# PCB-REMCON-ER.net
KiCad netlist of a schematic drawn in EAGLE
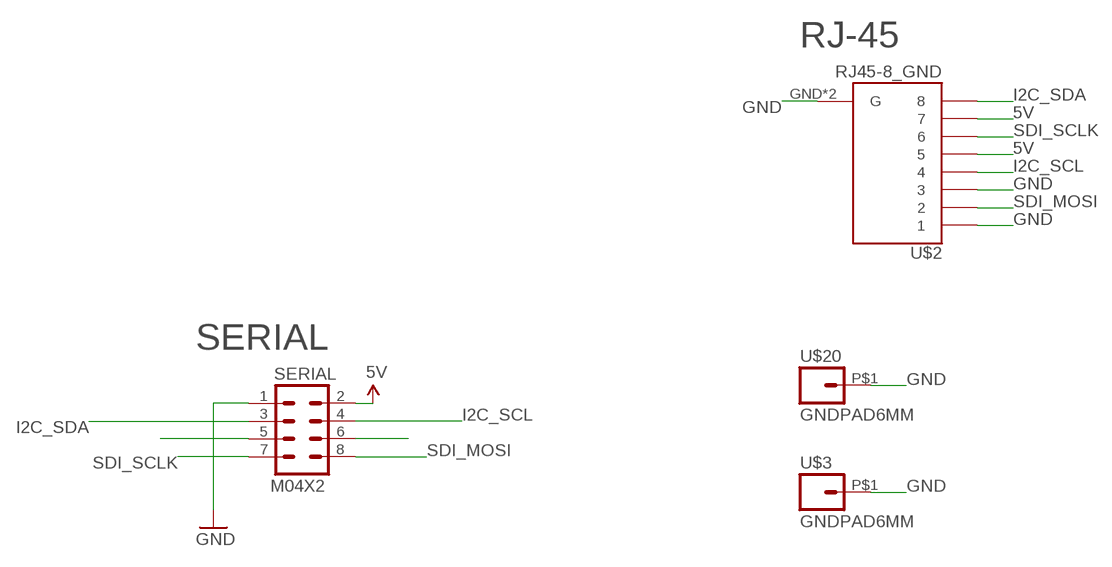
[diagram p0: schematic, sheet 1]

(export (version "E")
  (design (tool "Eeschema 10.0.6"))
  (components
    (comp (ref "SERIAL")
      (value "M04X2")
      (footprint "eagle-import:2X4")
      (libsource (lib "eagle-import") (part "M04X2"))
    )
    (comp (ref "U$2")
      (value "RJ45-8_GND")
      (footprint "eagle-import:RJ45-8_GND")
      (libsource (lib "eagle-import") (part "RJ45-8_GND"))
    )
    (comp (ref "U$3")
      (value "GNDPAD6MM")
      (footprint "eagle-import:3.2MMPAD6MM")
      (libsource (lib "eagle-import") (part "GNDPAD6MM"))
    )
    (comp (ref "U$20")
      (value "GNDPAD6MM")
      (footprint "eagle-import:3.2MMPAD6MM")
      (libsource (lib "eagle-import") (part "GNDPAD6MM"))
    )
  )
  (nets
    (net (code "1") (name "/I2C_SCL") (class "Default")
      (node (ref "SERIAL") (pin "4") (pinfunction "4_4") (pintype "passive"))
      (node (ref "U$2") (pin "4") (pinfunction "4_4") (pintype "bidirectional"))
    )
    (net (code "2") (name "/I2C_SDA") (class "Default")
      (node (ref "SERIAL") (pin "3") (pinfunction "3_3") (pintype "passive"))
      (node (ref "U$2") (pin "8") (pinfunction "8_8") (pintype "bidirectional"))
    )
    (net (code "3") (name "/SDI_MOSI") (class "Default")
      (node (ref "SERIAL") (pin "8") (pinfunction "8_8") (pintype "passive"))
      (node (ref "U$2") (pin "2") (pinfunction "2_2") (pintype "bidirectional"))
    )
    (net (code "4") (name "/SDI_SCLK") (class "Default")
      (node (ref "SERIAL") (pin "7") (pinfunction "7_7") (pintype "passive"))
      (node (ref "U$2") (pin "6") (pinfunction "6_6") (pintype "bidirectional"))
    )
    (net (code "5") (name "5V") (class "Default")
      (node (ref "SERIAL") (pin "2") (pinfunction "2_2") (pintype "passive"))
      (node (ref "U$2") (pin "5") (pinfunction "5_5") (pintype "bidirectional"))
      (node (ref "U$2") (pin "7") (pinfunction "7_7") (pintype "bidirectional"))
    )
    (net (code "6") (name "GND") (class "Default")
      (node (ref "SERIAL") (pin "1") (pinfunction "1_1") (pintype "passive"))
      (node (ref "U$2") (pin "1") (pinfunction "1_1") (pintype "bidirectional"))
      (node (ref "U$2") (pin "3") (pinfunction "3_3") (pintype "bidirectional"))
      (node (ref "U$2") (pin "GND") (pinfunction "G_GND") (pintype "power_in"))
      (node (ref "U$2") (pin "GND1") (pinfunction "G_GND1") (pintype "power_in"))
      (node (ref "U$20") (pin "P$1") (pinfunction "1_P$1") (pintype "passive"))
      (node (ref "U$3") (pin "P$1") (pinfunction "1_P$1") (pintype "passive"))
    )
    (net (code "7") (name "unconnected-(SERIAL-Pad5)") (class "Default")
      (node (ref "SERIAL") (pin "5") (pinfunction "5_5") (pintype "passive"))
    )
    (net (code "8") (name "unconnected-(SERIAL-Pad6)") (class "Default")
      (node (ref "SERIAL") (pin "6") (pinfunction "6_6") (pintype "passive"))
    )
  )
)
